# N76E003_Kit.net
KiCad netlist of a schematic drawn in Altium Designer
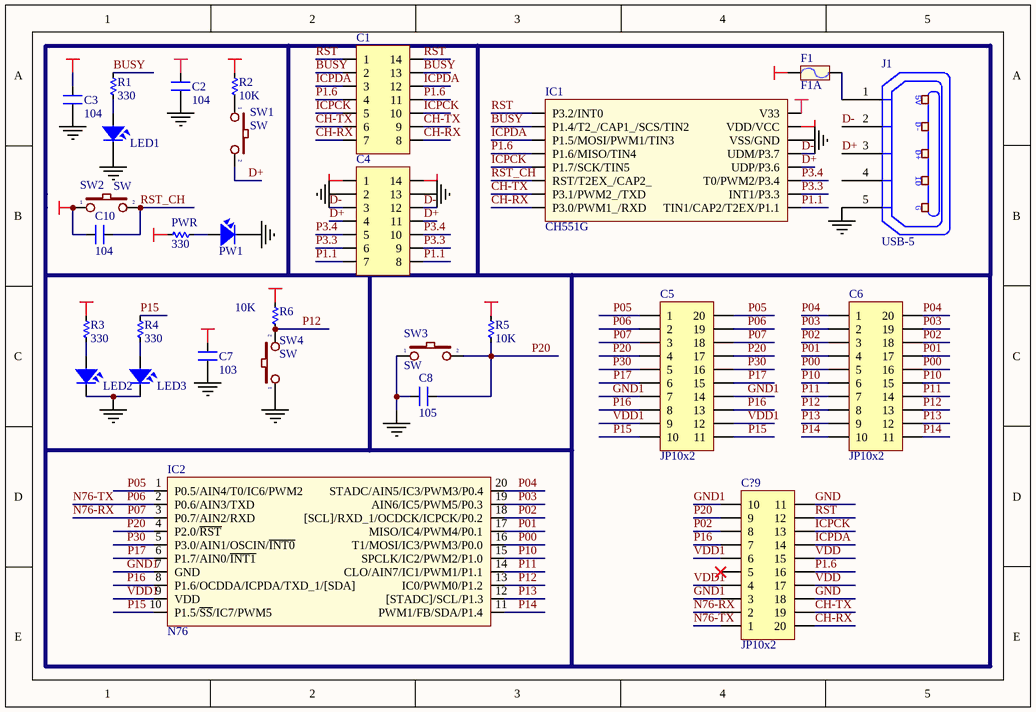
[diagram p0: [N76E003] Kit.SchDoc]

(export (version "E")
  (design (tool "Eeschema 10.0.6"))
  (components
    (comp (ref "C1")
      (value "JP7x2")
      (footprint "JP7-C2T")
      (description "WR-PHD 2.54 mm Dual Socket Header")
      (fields
        (field (name "MANUFACTURER") "Würth Elektronik eiSos GmbH")
        (field (name "PARTNO") "61301421821")
        (field (name "CREATED BY") "Karrer Zheng")
      )
      (libsource (lib "LIBRARY") (part "JP7x2"))
    )
    (comp (ref "C2")
      (value "104")
      (footprint "CN-SMD-0805")
      (description "Cap SMD")
      (libsource (lib "echipkool-com-library") (part "CM"))
    )
    (comp (ref "C3")
      (value "104")
      (footprint "CN-SMD-0805")
      (description "Cap SMD")
      (libsource (lib "echipkool-com-library") (part "CM"))
    )
    (comp (ref "C4")
      (value "JP7x2")
      (footprint "JP7-C2T")
      (description "WR-PHD 2.54 mm Dual Socket Header")
      (fields
        (field (name "MANUFACTURER") "Würth Elektronik eiSos GmbH")
        (field (name "PARTNO") "61301421821")
        (field (name "CREATED BY") "Karrer Zheng")
      )
      (libsource (lib "LIBRARY") (part "JP7x2"))
    )
    (comp (ref "C5")
      (value "JP10x2")
      (footprint "JP10-C2T")
      (description "WR-PHD 2.54 mm Dual Socket Header")
      (fields
        (field (name "MANUFACTURER") "Würth Elektronik eiSos GmbH")
        (field (name "PARTNO") "61302021821")
        (field (name "CREATED BY") "Karrer Zheng")
      )
      (libsource (lib "") (part "JP10x2_1"))
    )
    (comp (ref "C6")
      (value "JP10x2")
      (footprint "JP10-C2T")
      (description "WR-PHD 2.54 mm Dual Socket Header")
      (fields
        (field (name "MANUFACTURER") "Würth Elektronik eiSos GmbH")
        (field (name "PARTNO") "61302021821")
        (field (name "CREATED BY") "Karrer Zheng")
      )
      (libsource (lib "") (part "JP10x2_1"))
    )
    (comp (ref "C7")
      (value "103")
      (footprint "CN-SMD-0805")
      (description "Cap SMD")
      (libsource (lib "echipkool-com-library") (part "CM"))
    )
    (comp (ref "C8")
      (value "105")
      (footprint "CN-SMD-0805")
      (description "Cap SMD")
      (libsource (lib "echipkool-com-library") (part "CM"))
    )
    (comp (ref "C10")
      (value "104")
      (footprint "CN-SMD-0805")
      (description "Cap SMD")
      (libsource (lib "echipkool-com-library") (part "CM"))
    )
    (comp (ref "C?9")
      (value "JP10x2")
      (footprint "JP10-D2T")
      (description "WR-PHD 2.54 mm Dual Socket Header")
      (fields
        (field (name "MANUFACTURER") "Würth Elektronik eiSos GmbH")
        (field (name "PARTNO") "61302021821")
        (field (name "CREATED BY") "Karrer Zheng")
      )
      (libsource (lib "LIBRARY") (part "JP10x2"))
    )
    (comp (ref "F1")
      (value "F1A")
      (footprint "SM-RES-1206")
      (description "Fuse")
      (fields (field (name "DESIGNED BY") "VanDungEvn"))
      (libsource (lib "LIBRARY") (part "Fuse"))
    )
    (comp (ref "IC1") (value "CH551G") (footprint "Jmi:SOP16") (libsource (lib "Jmi") (part "[MCU] CH551G")))
    (comp (ref "IC2") (value "N76") (footprint "Jmi:TSSOP20") (libsource (lib "Jmi") (part "[MCU] N76E003")))
    (comp (ref "J1")
      (value "USB-5")
      (footprint "USB-M3")
      (fields
        (field (name "MANUFACTURER") "FCI")
        (field (name "MANUFACTURER PART NUMBER") "10118193-0001LF")
        (field (name ".CREATOR") "MM")
        (field (name ".CHECKED PCB") "RF")
        (field (name ".CHECKED SCH") "MM")
      )
      (libsource (lib "LIBRARY") (part "USB-5"))
    )
    (comp (ref "LED1")
      (value "LED")
      (footprint "LED-0805-Green")
      (libsource (lib "LIBRARY") (part "LED SMD"))
    )
    (comp (ref "LED2") (value "LED") (footprint "LED-0805-Red") (libsource (lib "LIBRARY") (part "LED SMD")))
    (comp (ref "LED3") (value "LED") (footprint "LED-0805-Blue") (libsource (lib "LIBRARY") (part "LED SMD")))
    (comp (ref "PW1") (value "LED") (footprint "LED-0805-Green") (libsource (lib "LIBRARY") (part "LED SMD")))
    (comp (ref "PWR")
      (value "330")
      (footprint "RES-SMD-0805")
      (description "Resistor")
      (fields
        (field (name "MANUFACTURER") "Generic Components")
        (field (name "PUBLISHER") "Altium Hobart Technology Centre")
      )
      (libsource (lib "LIBRARY") (part "Res-SMD"))
    )
    (comp (ref "R1")
      (value "330")
      (footprint "RES-SMD-0805")
      (description "Resistor")
      (fields
        (field (name "MANUFACTURER") "Generic Components")
        (field (name "PUBLISHER") "Altium Hobart Technology Centre")
      )
      (libsource (lib "LIBRARY") (part "Res-SMD"))
    )
    (comp (ref "R2")
      (value "10K")
      (footprint "RES-SMD-0805")
      (description "Resistor")
      (fields
        (field (name "MANUFACTURER") "Generic Components")
        (field (name "PUBLISHER") "Altium Hobart Technology Centre")
      )
      (libsource (lib "LIBRARY") (part "Res-SMD"))
    )
    (comp (ref "R3")
      (value "330")
      (footprint "RES-SMD-0805")
      (description "Resistor")
      (fields
        (field (name "MANUFACTURER") "Generic Components")
        (field (name "PUBLISHER") "Altium Hobart Technology Centre")
      )
      (libsource (lib "LIBRARY") (part "Res-SMD"))
    )
    (comp (ref "R4")
      (value "330")
      (footprint "RES-SMD-0805")
      (description "Resistor")
      (fields
        (field (name "MANUFACTURER") "Generic Components")
        (field (name "PUBLISHER") "Altium Hobart Technology Centre")
      )
      (libsource (lib "LIBRARY") (part "Res-SMD"))
    )
    (comp (ref "R5")
      (value "10K")
      (footprint "RES-SMD-0805")
      (description "Resistor")
      (fields
        (field (name "MANUFACTURER") "Generic Components")
        (field (name "PUBLISHER") "Altium Hobart Technology Centre")
      )
      (libsource (lib "LIBRARY") (part "Res-SMD"))
    )
    (comp (ref "R6")
      (value "10K")
      (footprint "RES-SMD-0805")
      (description "Resistor")
      (fields
        (field (name "MANUFACTURER") "Generic Components")
        (field (name "PUBLISHER") "Altium Hobart Technology Centre")
      )
      (libsource (lib "LIBRARY") (part "Res-SMD"))
    )
    (comp (ref "SW1")
      (value "SW")
      (footprint "SW1-SMD")
      (description "Switch button 2 pin")
      (libsource (lib "LIBRARY") (part "SW2"))
    )
    (comp (ref "SW2")
      (value "SW")
      (footprint "SW1-SMD")
      (description "Switch button 2 pin")
      (libsource (lib "LIBRARY") (part "SW2"))
    )
    (comp (ref "SW3")
      (value "SW")
      (footprint "SW1-SMD")
      (description "Switch button 2 pin")
      (libsource (lib "LIBRARY") (part "SW2"))
    )
    (comp (ref "SW4")
      (value "SW")
      (footprint "SW1-SMD")
      (description "Switch button 2 pin")
      (libsource (lib "LIBRARY") (part "SW2"))
    )
  )
  (nets
    (net (code "1") (name "+3.3v") (class "Default")
      (node (ref "C2") (pin "2") (pinfunction "2_2") (pintype "passive"))
      (node (ref "IC1") (pin "16") (pinfunction "V33_16") (pintype "power_in"))
    )
    (net (code "2") (name "/BUSY") (class "Default")
      (node (ref "C1") (pin "13") (pinfunction "13_13") (pintype "passive"))
      (node (ref "C1") (pin "2") (pinfunction "2_2") (pintype "passive"))
      (node (ref "IC1") (pin "2") (pinfunction "P1.4/T2_/CAP1_/SCS/TIN2_2") (pintype "power_in"))
      (node (ref "R1") (pin "1") (pinfunction "1_1") (pintype "passive"))
    )
    (net (code "3") (name "/CH-RX") (class "Default")
      (node (ref "C1") (pin "7") (pinfunction "7_7") (pintype "passive"))
      (node (ref "C1") (pin "8") (pinfunction "8_8") (pintype "passive"))
      (node (ref "C?9") (pin "20") (pinfunction "20_20") (pintype "passive"))
      (node (ref "IC1") (pin "8") (pinfunction "P3.0/PWM1_/RXD_8") (pintype "power_in"))
    )
    (net (code "4") (name "/CH-TX") (class "Default")
      (node (ref "C1") (pin "6") (pinfunction "6_6") (pintype "passive"))
      (node (ref "C1") (pin "9") (pinfunction "9_9") (pintype "passive"))
      (node (ref "C?9") (pin "19") (pinfunction "19_19") (pintype "passive"))
      (node (ref "IC1") (pin "7") (pinfunction "P3.1/PWM2_/TXD_7") (pintype "power_in"))
    )
    (net (code "5") (name "/D+") (class "Default")
      (node (ref "C4") (pin "11") (pinfunction "11_11") (pintype "passive"))
      (node (ref "C4") (pin "4") (pinfunction "4_4") (pintype "passive"))
      (node (ref "IC1") (pin "12") (pinfunction "UDP/P3.6_12") (pintype "power_in"))
      (node (ref "J1") (pin "3") (pinfunction "P3_3") (pintype "passive"))
      (node (ref "SW1") (pin "2") (pinfunction "2_2") (pintype "passive"))
    )
    (net (code "6") (name "/D-") (class "Default")
      (node (ref "C4") (pin "12") (pinfunction "12_12") (pintype "passive"))
      (node (ref "C4") (pin "3") (pinfunction "3_3") (pintype "passive"))
      (node (ref "IC1") (pin "13") (pinfunction "UDM/P3.7_13") (pintype "power_in"))
      (node (ref "J1") (pin "2") (pinfunction "P2_2") (pintype "passive"))
    )
    (net (code "7") (name "/ICPCK") (class "Default")
      (node (ref "C1") (pin "10") (pinfunction "10_10") (pintype "passive"))
      (node (ref "C1") (pin "5") (pinfunction "5_5") (pintype "passive"))
      (node (ref "C?9") (pin "13") (pinfunction "13_13") (pintype "passive"))
      (node (ref "IC1") (pin "5") (pinfunction "P1.7/SCK/TIN5_5") (pintype "power_in"))
    )
    (net (code "8") (name "/ICPDA") (class "Default")
      (node (ref "C1") (pin "12") (pinfunction "12_12") (pintype "passive"))
      (node (ref "C1") (pin "3") (pinfunction "3_3") (pintype "passive"))
      (node (ref "C?9") (pin "14") (pinfunction "14_14") (pintype "passive"))
      (node (ref "IC1") (pin "3") (pinfunction "P1.5/MOSI/PWM1/TIN3_3") (pintype "power_in"))
    )
    (net (code "9") (name "/N76-RX") (class "Default")
      (node (ref "C5") (pin "18") (pinfunction "18_18") (pintype "passive"))
      (node (ref "C5") (pin "3") (pinfunction "3_3") (pintype "passive"))
      (node (ref "C?9") (pin "2") (pinfunction "2_2") (pintype "passive"))
      (node (ref "IC2") (pin "3") (pinfunction "P0.7/AIN2/RXD_3") (pintype "passive"))
    )
    (net (code "10") (name "/N76-TX") (class "Default")
      (node (ref "C5") (pin "19") (pinfunction "19_19") (pintype "passive"))
      (node (ref "C5") (pin "2") (pinfunction "2_2") (pintype "passive"))
      (node (ref "C?9") (pin "1") (pinfunction "1_1") (pintype "passive"))
      (node (ref "IC2") (pin "2") (pinfunction "P0.6/AIN3/TXD_2") (pintype "passive"))
    )
    (net (code "11") (name "/P00") (class "Default")
      (node (ref "C6") (pin "16") (pinfunction "16_16") (pintype "passive"))
      (node (ref "C6") (pin "5") (pinfunction "5_5") (pintype "passive"))
      (node (ref "IC2") (pin "16") (pinfunction "T1/MOSI/IC3/PWM3/P0.0_16") (pintype "passive"))
    )
    (net (code "12") (name "/P01") (class "Default")
      (node (ref "C6") (pin "17") (pinfunction "17_17") (pintype "passive"))
      (node (ref "C6") (pin "4") (pinfunction "4_4") (pintype "passive"))
      (node (ref "IC2") (pin "17") (pinfunction "MISO/IC4/PWM4/P0.1_17") (pintype "passive"))
    )
    (net (code "13") (name "/P1.1") (class "Default")
      (node (ref "C4") (pin "7") (pinfunction "7_7") (pintype "passive"))
      (node (ref "C4") (pin "8") (pinfunction "8_8") (pintype "passive"))
      (node (ref "IC1") (pin "9") (pinfunction "TIN1/CAP2/T2EX/P1.1_9") (pintype "power_in"))
    )
    (net (code "14") (name "/P1.6") (class "Default")
      (node (ref "C1") (pin "11") (pinfunction "11_11") (pintype "passive"))
      (node (ref "C1") (pin "4") (pinfunction "4_4") (pintype "passive"))
      (node (ref "C?9") (pin "16") (pinfunction "16_16") (pintype "passive"))
      (node (ref "IC1") (pin "4") (pinfunction "P1.6/MISO/TIN4_4") (pintype "power_in"))
    )
    (net (code "15") (name "/P02") (class "Default")
      (node (ref "C6") (pin "18") (pinfunction "18_18") (pintype "passive"))
      (node (ref "C6") (pin "3") (pinfunction "3_3") (pintype "passive"))
      (node (ref "C?9") (pin "8") (pinfunction "8_8") (pintype "passive"))
      (node (ref "IC2") (pin "18") (pinfunction "[SCL]/RXD_1/OCDCK/ICPCK/P0.2_18") (pintype "passive"))
    )
    (net (code "16") (name "/P03") (class "Default")
      (node (ref "C6") (pin "19") (pinfunction "19_19") (pintype "passive"))
      (node (ref "C6") (pin "2") (pinfunction "2_2") (pintype "passive"))
      (node (ref "IC2") (pin "19") (pinfunction "AIN6/IC5/PWM5/P0.3_19") (pintype "passive"))
    )
    (net (code "17") (name "/P3.3") (class "Default")
      (node (ref "C4") (pin "6") (pinfunction "6_6") (pintype "passive"))
      (node (ref "C4") (pin "9") (pinfunction "9_9") (pintype "passive"))
      (node (ref "IC1") (pin "10") (pinfunction "INT1/P3.3_10") (pintype "power_in"))
    )
    (net (code "18") (name "/P3.4") (class "Default")
      (node (ref "C4") (pin "10") (pinfunction "10_10") (pintype "passive"))
      (node (ref "C4") (pin "5") (pinfunction "5_5") (pintype "passive"))
      (node (ref "IC1") (pin "11") (pinfunction "T0/PWM2/P3.4_11") (pintype "power_in"))
    )
    (net (code "19") (name "/P04") (class "Default")
      (node (ref "C6") (pin "1") (pinfunction "1_1") (pintype "passive"))
      (node (ref "C6") (pin "20") (pinfunction "20_20") (pintype "passive"))
      (node (ref "IC2") (pin "20") (pinfunction "STADC/AIN5/IC3/PWM3/P0.4_20") (pintype "passive"))
    )
    (net (code "20") (name "/P05") (class "Default")
      (node (ref "C5") (pin "1") (pinfunction "1_1") (pintype "passive"))
      (node (ref "C5") (pin "20") (pinfunction "20_20") (pintype "passive"))
      (node (ref "IC2") (pin "1") (pinfunction "P0.5/AIN4/T0/IC6/PWM2_1") (pintype "passive"))
    )
    (net (code "21") (name "/P10") (class "Default")
      (node (ref "C6") (pin "15") (pinfunction "15_15") (pintype "passive"))
      (node (ref "C6") (pin "6") (pinfunction "6_6") (pintype "passive"))
      (node (ref "IC2") (pin "15") (pinfunction "SPCLK/IC2/PWM2/P1.0_15") (pintype "passive"))
    )
    (net (code "22") (name "/P11") (class "Default")
      (node (ref "C6") (pin "14") (pinfunction "14_14") (pintype "passive"))
      (node (ref "C6") (pin "7") (pinfunction "7_7") (pintype "passive"))
      (node (ref "IC2") (pin "14") (pinfunction "CLO/AIN7/IC1/PWM1/P1.1_14") (pintype "passive"))
    )
    (net (code "23") (name "/P12") (class "Default")
      (node (ref "C6") (pin "13") (pinfunction "13_13") (pintype "passive"))
      (node (ref "C6") (pin "8") (pinfunction "8_8") (pintype "passive"))
      (node (ref "IC2") (pin "13") (pinfunction "IC0/PWM0/P1.2_13") (pintype "passive"))
      (node (ref "R6") (pin "2") (pinfunction "2_2") (pintype "passive"))
      (node (ref "SW4") (pin "2") (pinfunction "2_2") (pintype "passive"))
    )
    (net (code "24") (name "/P13") (class "Default")
      (node (ref "C6") (pin "12") (pinfunction "12_12") (pintype "passive"))
      (node (ref "C6") (pin "9") (pinfunction "9_9") (pintype "passive"))
      (node (ref "IC2") (pin "12") (pinfunction "[STADC]/SCL/P1.3_12") (pintype "passive"))
    )
    (net (code "25") (name "/P14") (class "Default")
      (node (ref "C6") (pin "10") (pinfunction "10_10") (pintype "passive"))
      (node (ref "C6") (pin "11") (pinfunction "11_11") (pintype "passive"))
      (node (ref "IC2") (pin "11") (pinfunction "PWM1/FB/SDA/P1.4_11") (pintype "passive"))
    )
    (net (code "26") (name "/P15") (class "Default")
      (node (ref "C5") (pin "10") (pinfunction "10_10") (pintype "passive"))
      (node (ref "C5") (pin "11") (pinfunction "11_11") (pintype "passive"))
      (node (ref "IC2") (pin "10") (pinfunction "P1.5/~{SS}/IC7/PWM5_10") (pintype "passive"))
      (node (ref "R4") (pin "1") (pinfunction "1_1") (pintype "passive"))
    )
    (net (code "27") (name "/P16") (class "Default")
      (node (ref "C5") (pin "13") (pinfunction "13_13") (pintype "passive"))
      (node (ref "C5") (pin "8") (pinfunction "8_8") (pintype "passive"))
      (node (ref "C?9") (pin "7") (pinfunction "7_7") (pintype "passive"))
      (node (ref "IC2") (pin "8") (pinfunction "P1.6/OCDDA/ICPDA/TXD_1/[SDA]_8") (pintype "passive"))
    )
    (net (code "28") (name "/P17") (class "Default")
      (node (ref "C5") (pin "15") (pinfunction "15_15") (pintype "passive"))
      (node (ref "C5") (pin "6") (pinfunction "6_6") (pintype "passive"))
      (node (ref "IC2") (pin "6") (pinfunction "P1.7/AIN0/~{INT1}_6") (pintype "passive"))
    )
    (net (code "29") (name "/P20") (class "Default")
      (node (ref "C5") (pin "17") (pinfunction "17_17") (pintype "passive"))
      (node (ref "C5") (pin "4") (pinfunction "4_4") (pintype "passive"))
      (node (ref "C8") (pin "1") (pinfunction "1_1") (pintype "passive"))
      (node (ref "C?9") (pin "9") (pinfunction "9_9") (pintype "passive"))
      (node (ref "IC2") (pin "4") (pinfunction "P2.0/~{RST}_4") (pintype "passive"))
      (node (ref "R5") (pin "2") (pinfunction "2_2") (pintype "passive"))
      (node (ref "SW3") (pin "2") (pinfunction "2_2") (pintype "passive"))
    )
    (net (code "30") (name "/P30") (class "Default")
      (node (ref "C5") (pin "16") (pinfunction "16_16") (pintype "passive"))
      (node (ref "C5") (pin "5") (pinfunction "5_5") (pintype "passive"))
      (node (ref "IC2") (pin "5") (pinfunction "P3.0/AIN1/OSCIN/~{INT0}_5") (pintype "passive"))
    )
    (net (code "31") (name "/RST") (class "Default")
      (node (ref "C1") (pin "1") (pinfunction "1_1") (pintype "passive"))
      (node (ref "C1") (pin "14") (pinfunction "14_14") (pintype "passive"))
      (node (ref "C?9") (pin "12") (pinfunction "12_12") (pintype "passive"))
      (node (ref "IC1") (pin "1") (pinfunction "P3.2/INT0_1") (pintype "power_in"))
    )
    (net (code "32") (name "/RST_CH") (class "Default")
      (node (ref "C10") (pin "1") (pinfunction "1_1") (pintype "passive"))
      (node (ref "IC1") (pin "6") (pinfunction "RST/T2EX_/CAP2__6") (pintype "power_in"))
      (node (ref "SW2") (pin "2") (pinfunction "2_2") (pintype "passive"))
    )
    (net (code "33") (name "GND") (class "Default")
      (node (ref "C2") (pin "1") (pinfunction "1_1") (pintype "passive"))
      (node (ref "C3") (pin "1") (pinfunction "1_1") (pintype "passive"))
      (node (ref "C4") (pin "13") (pinfunction "13_13") (pintype "passive"))
      (node (ref "C4") (pin "2") (pinfunction "2_2") (pintype "passive"))
      (node (ref "C?9") (pin "11") (pinfunction "11_11") (pintype "passive"))
      (node (ref "C?9") (pin "18") (pinfunction "18_18") (pintype "passive"))
      (node (ref "IC1") (pin "14") (pinfunction "VSS/GND_14") (pintype "power_in"))
      (node (ref "J1") (pin "5") (pinfunction "P5_5") (pintype "passive"))
      (node (ref "LED1") (pin "2") (pinfunction "2_2") (pintype "passive"))
      (node (ref "PW1") (pin "2") (pinfunction "2_2") (pintype "passive"))
    )
    (net (code "34") (name "GND1") (class "Default")
      (node (ref "C5") (pin "14") (pinfunction "14_14") (pintype "passive"))
      (node (ref "C5") (pin "7") (pinfunction "7_7") (pintype "passive"))
      (node (ref "C7") (pin "1") (pinfunction "1_1") (pintype "passive"))
      (node (ref "C8") (pin "2") (pinfunction "2_2") (pintype "passive"))
      (node (ref "C?9") (pin "10") (pinfunction "10_10") (pintype "passive"))
      (node (ref "C?9") (pin "3") (pinfunction "3_3") (pintype "passive"))
      (node (ref "IC2") (pin "7") (pinfunction "GND_7") (pintype "power_in"))
      (node (ref "LED2") (pin "2") (pinfunction "2_2") (pintype "passive"))
      (node (ref "LED3") (pin "2") (pinfunction "2_2") (pintype "passive"))
      (node (ref "SW3") (pin "1") (pinfunction "1_1") (pintype "passive"))
      (node (ref "SW4") (pin "1") (pinfunction "1_1") (pintype "passive"))
    )
    (net (code "35") (name "Net-(J1-P1)") (class "Default")
      (node (ref "F1") (pin "1") (pinfunction "1_1") (pintype "passive"))
      (node (ref "J1") (pin "1") (pinfunction "P1_1") (pintype "passive"))
    )
    (net (code "36") (name "Net-(LED1-Pad1)") (class "Default")
      (node (ref "LED1") (pin "1") (pinfunction "1_1") (pintype "passive"))
      (node (ref "R1") (pin "2") (pinfunction "2_2") (pintype "passive"))
    )
    (net (code "37") (name "Net-(LED2-Pad1)") (class "Default")
      (node (ref "LED2") (pin "1") (pinfunction "1_1") (pintype "passive"))
      (node (ref "R3") (pin "2") (pinfunction "2_2") (pintype "passive"))
    )
    (net (code "38") (name "Net-(LED3-Pad1)") (class "Default")
      (node (ref "LED3") (pin "1") (pinfunction "1_1") (pintype "passive"))
      (node (ref "R4") (pin "2") (pinfunction "2_2") (pintype "passive"))
    )
    (net (code "39") (name "Net-(PW1-Pad1)") (class "Default")
      (node (ref "PW1") (pin "1") (pinfunction "1_1") (pintype "passive"))
      (node (ref "PWR") (pin "2") (pinfunction "2_2") (pintype "passive"))
    )
    (net (code "40") (name "Net-(R2-Pad2)") (class "Default")
      (node (ref "R2") (pin "2") (pinfunction "2_2") (pintype "passive"))
      (node (ref "SW1") (pin "1") (pinfunction "1_1") (pintype "passive"))
    )
    (net (code "41") (name "VDD") (class "Default")
      (node (ref "C10") (pin "2") (pinfunction "2_2") (pintype "passive"))
      (node (ref "C3") (pin "2") (pinfunction "2_2") (pintype "passive"))
      (node (ref "C4") (pin "1") (pinfunction "1_1") (pintype "passive"))
      (node (ref "C4") (pin "14") (pinfunction "14_14") (pintype "passive"))
      (node (ref "C?9") (pin "15") (pinfunction "15_15") (pintype "passive"))
      (node (ref "C?9") (pin "17") (pinfunction "17_17") (pintype "passive"))
      (node (ref "F1") (pin "2") (pinfunction "2_2") (pintype "passive"))
      (node (ref "IC1") (pin "15") (pinfunction "VDD/VCC_15") (pintype "power_in"))
      (node (ref "PWR") (pin "1") (pinfunction "1_1") (pintype "passive"))
      (node (ref "R2") (pin "1") (pinfunction "1_1") (pintype "passive"))
      (node (ref "SW2") (pin "1") (pinfunction "1_1") (pintype "passive"))
    )
    (net (code "42") (name "VDD1") (class "Default")
      (node (ref "C5") (pin "12") (pinfunction "12_12") (pintype "passive"))
      (node (ref "C5") (pin "9") (pinfunction "9_9") (pintype "passive"))
      (node (ref "C7") (pin "2") (pinfunction "2_2") (pintype "passive"))
      (node (ref "C?9") (pin "4") (pinfunction "4_4") (pintype "passive"))
      (node (ref "C?9") (pin "6") (pinfunction "6_6") (pintype "passive"))
      (node (ref "IC2") (pin "9") (pinfunction "VDD_9") (pintype "power_in"))
      (node (ref "R3") (pin "1") (pinfunction "1_1") (pintype "passive"))
      (node (ref "R5") (pin "1") (pinfunction "1_1") (pintype "passive"))
      (node (ref "R6") (pin "1") (pinfunction "1_1") (pintype "passive"))
    )
    (net (code "43") (name "unconnected-(C?9-Pad5)") (class "Default")
      (node (ref "C?9") (pin "5") (pinfunction "5_5") (pintype "passive+no_connect"))
    )
    (net (code "44") (name "unconnected-(J1-P4-Pad4)") (class "Default")
      (node (ref "J1") (pin "4") (pinfunction "P4_4") (pintype "passive"))
    )
  )
)
